# Link232-wifi-c64.net
KiCad netlist of a schematic drawn in EAGLE
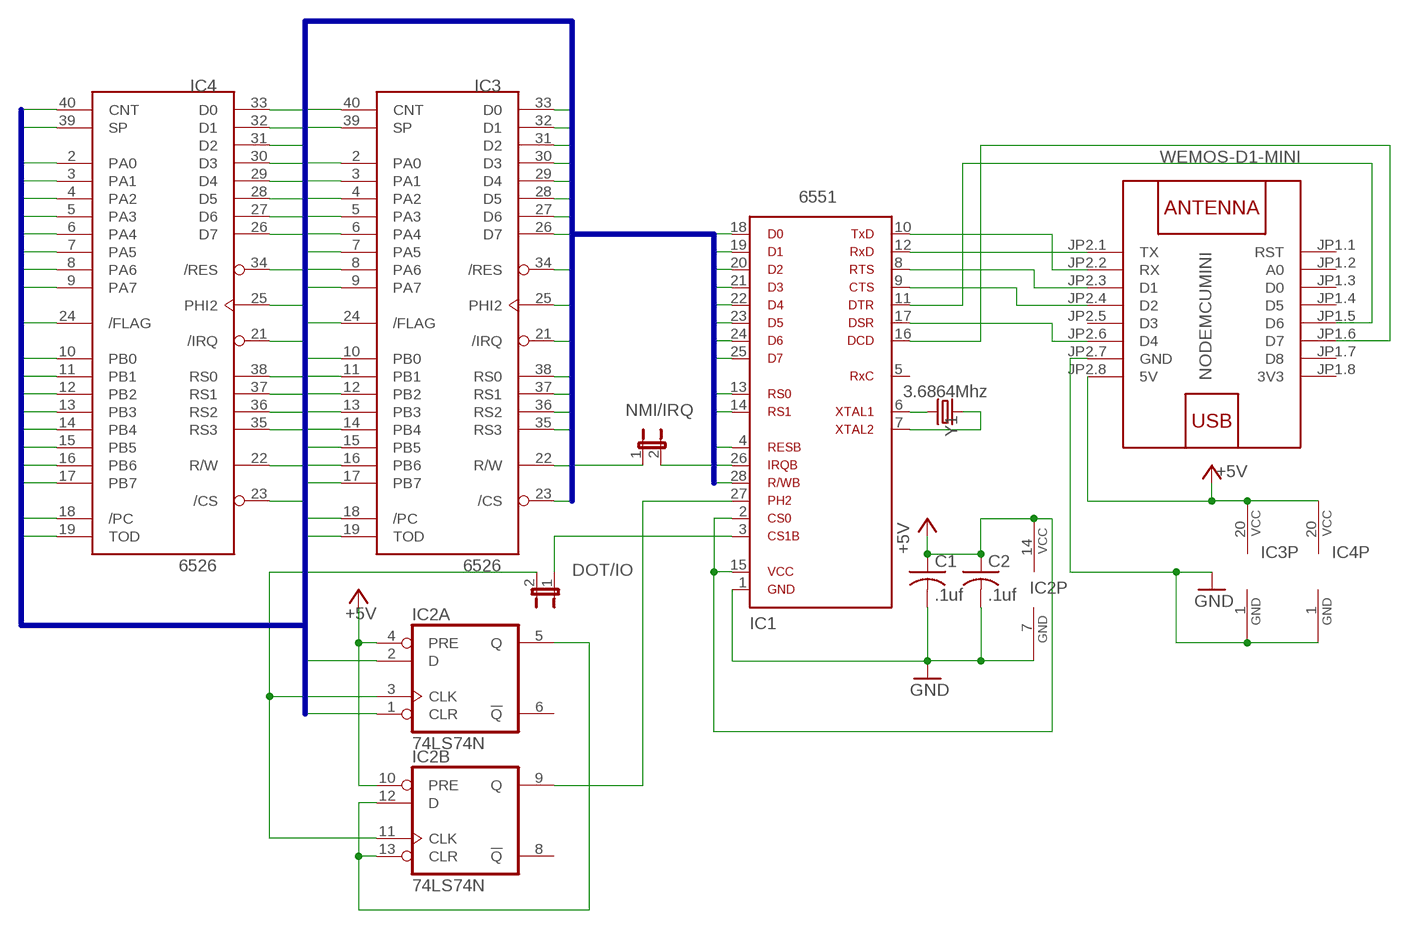
[diagram p0: schematic, sheet 1]

(export (version "E")
  (design (tool "Eeschema 10.0.6"))
  (components
    (comp (ref "C1")
      (value ".1uf")
      (footprint "eagle-import:C050-024X044")
      (libsource (lib "eagle-import") (part "C-US050-024X044"))
    )
    (comp (ref "C2")
      (value ".1uf")
      (footprint "eagle-import:C050-024X044")
      (libsource (lib "eagle-import") (part "C-US050-024X044"))
    )
    (comp (ref "IC1")
      (value "6551")
      (footprint "eagle-import:6551")
      (libsource (lib "eagle-import") (part "6551"))
    )
    (comp (ref "IC2")
      (value "74LS74N")
      (footprint "eagle-import:DIL14")
      (libsource (lib "eagle-import") (part "7474NLS"))
    )
    (comp (ref "IC3")
      (value "6526")
      (footprint "eagle-import:DIP40")
      (libsource (lib "eagle-import") (part "6526"))
    )
    (comp (ref "IC4")
      (value "6526")
      (footprint "eagle-import:DIP40")
      (libsource (lib "eagle-import") (part "6526"))
    )
    (comp (ref "JP1")
      (value "NMI/IRQ")
      (footprint "eagle-import:JP1")
      (libsource (lib "eagle-import") (part "JP1E"))
    )
    (comp (ref "JP2")
      (value "DOT/IO")
      (footprint "eagle-import:JP1")
      (libsource (lib "eagle-import") (part "JP1E"))
    )
    (comp (ref "NODEMCUMINI")
      (value "WEMOS-D1-MINI")
      (footprint "eagle-import:WEMOS-D1-MINI")
      (libsource (lib "eagle-import") (part "WEMOS-D1-MINI"))
    )
    (comp (ref "Y1")
      (value "3.6864Mhz")
      (footprint "eagle-import:HC49US")
      (libsource (lib "eagle-import") (part "CRYSTALPTH-HC49US"))
    )
  )
  (nets
    (net (code "1") (name "+5V") (class "Default")
      (node (ref "C1") (pin "1") (pinfunction "1_1") (pintype "passive"))
      (node (ref "C2") (pin "1") (pinfunction "1_1") (pintype "passive"))
      (node (ref "IC1") (pin "15") (pinfunction "15_15") (pintype "passive"))
      (node (ref "IC1") (pin "2") (pinfunction "2_2") (pintype "passive"))
      (node (ref "IC2") (pin "10") (pinfunction "PRE_10") (pintype "input"))
      (node (ref "IC2") (pin "14") (pinfunction "VCC_14") (pintype "power_in"))
      (node (ref "IC2") (pin "4") (pinfunction "PRE_4") (pintype "input"))
      (node (ref "IC3") (pin "20") (pinfunction "VCC_20") (pintype "power_in"))
      (node (ref "IC4") (pin "20") (pinfunction "VCC_20") (pintype "power_in"))
      (node (ref "NODEMCUMINI") (pin "JP2.8") (pinfunction "5V_JP2.8") (pintype "power_in"))
    )
    (net (code "2") (name "/3V3") (class "Default")
      (node (ref "NODEMCUMINI") (pin "JP1.8") (pinfunction "3V3_JP1.8") (pintype "power_in"))
    )
    (net (code "3") (name "/CNT") (class "Default")
      (node (ref "IC3") (pin "40") (pinfunction "CNT_40") (pintype "input"))
      (node (ref "IC4") (pin "40") (pinfunction "CNT_40") (pintype "input"))
    )
    (net (code "4") (name "/D0") (class "Default")
      (node (ref "IC1") (pin "18") (pinfunction "18_18") (pintype "passive"))
      (node (ref "IC3") (pin "33") (pinfunction "D0_33") (pintype "bidirectional"))
      (node (ref "IC4") (pin "33") (pinfunction "D0_33") (pintype "bidirectional"))
    )
    (net (code "5") (name "/D1") (class "Default")
      (node (ref "IC1") (pin "19") (pinfunction "19_19") (pintype "passive"))
      (node (ref "IC3") (pin "32") (pinfunction "D1_32") (pintype "bidirectional"))
      (node (ref "IC4") (pin "32") (pinfunction "D1_32") (pintype "bidirectional"))
    )
    (net (code "6") (name "/D2") (class "Default")
      (node (ref "IC1") (pin "20") (pinfunction "20_20") (pintype "passive"))
      (node (ref "IC3") (pin "31") (pinfunction "D2_31") (pintype "bidirectional"))
      (node (ref "IC4") (pin "31") (pinfunction "D2_31") (pintype "bidirectional"))
    )
    (net (code "7") (name "/D3") (class "Default")
      (node (ref "IC1") (pin "21") (pinfunction "21_21") (pintype "passive"))
      (node (ref "IC3") (pin "30") (pinfunction "D3_30") (pintype "bidirectional"))
      (node (ref "IC4") (pin "30") (pinfunction "D3_30") (pintype "bidirectional"))
    )
    (net (code "8") (name "/D4") (class "Default")
      (node (ref "IC1") (pin "22") (pinfunction "22_22") (pintype "passive"))
      (node (ref "IC3") (pin "29") (pinfunction "D4_29") (pintype "bidirectional"))
      (node (ref "IC4") (pin "29") (pinfunction "D4_29") (pintype "bidirectional"))
    )
    (net (code "9") (name "/D5") (class "Default")
      (node (ref "IC1") (pin "23") (pinfunction "23_23") (pintype "passive"))
      (node (ref "IC3") (pin "28") (pinfunction "D5_28") (pintype "bidirectional"))
      (node (ref "IC4") (pin "28") (pinfunction "D5_28") (pintype "bidirectional"))
    )
    (net (code "10") (name "/D6") (class "Default")
      (node (ref "IC1") (pin "24") (pinfunction "24_24") (pintype "passive"))
      (node (ref "IC3") (pin "27") (pinfunction "D6_27") (pintype "bidirectional"))
      (node (ref "IC4") (pin "27") (pinfunction "D6_27") (pintype "bidirectional"))
    )
    (net (code "11") (name "/D7") (class "Default")
      (node (ref "IC1") (pin "25") (pinfunction "25_25") (pintype "passive"))
      (node (ref "IC3") (pin "26") (pinfunction "D7_26") (pintype "bidirectional"))
      (node (ref "IC4") (pin "26") (pinfunction "D7_26") (pintype "bidirectional"))
    )
    (net (code "12") (name "/IRQ") (class "Default")
      (node (ref "IC3") (pin "21") (pinfunction "/IRQ_21") (pintype "open_collector"))
      (node (ref "IC4") (pin "21") (pinfunction "/IRQ_21") (pintype "open_collector"))
      (node (ref "JP1") (pin "1") (pinfunction "1_1") (pintype "passive"))
    )
    (net (code "13") (name "/PA0") (class "Default")
      (node (ref "IC3") (pin "2") (pinfunction "PA0_2") (pintype "bidirectional"))
      (node (ref "IC4") (pin "2") (pinfunction "PA0_2") (pintype "bidirectional"))
    )
    (net (code "14") (name "/PA1") (class "Default")
      (node (ref "IC3") (pin "3") (pinfunction "PA1_3") (pintype "bidirectional"))
      (node (ref "IC4") (pin "3") (pinfunction "PA1_3") (pintype "bidirectional"))
    )
    (net (code "15") (name "/PA2") (class "Default")
      (node (ref "IC3") (pin "4") (pinfunction "PA2_4") (pintype "bidirectional"))
      (node (ref "IC4") (pin "4") (pinfunction "PA2_4") (pintype "bidirectional"))
    )
    (net (code "16") (name "/PA3") (class "Default")
      (node (ref "IC3") (pin "5") (pinfunction "PA3_5") (pintype "bidirectional"))
      (node (ref "IC4") (pin "5") (pinfunction "PA3_5") (pintype "bidirectional"))
    )
    (net (code "17") (name "/PA4") (class "Default")
      (node (ref "IC3") (pin "6") (pinfunction "PA4_6") (pintype "bidirectional"))
      (node (ref "IC4") (pin "6") (pinfunction "PA4_6") (pintype "bidirectional"))
    )
    (net (code "18") (name "/PA5") (class "Default")
      (node (ref "IC3") (pin "7") (pinfunction "PA5_7") (pintype "bidirectional"))
      (node (ref "IC4") (pin "7") (pinfunction "PA5_7") (pintype "bidirectional"))
    )
    (net (code "19") (name "/PA6") (class "Default")
      (node (ref "IC3") (pin "8") (pinfunction "PA6_8") (pintype "bidirectional"))
      (node (ref "IC4") (pin "8") (pinfunction "PA6_8") (pintype "bidirectional"))
    )
    (net (code "20") (name "/PA7") (class "Default")
      (node (ref "IC3") (pin "9") (pinfunction "PA7_9") (pintype "bidirectional"))
      (node (ref "IC4") (pin "9") (pinfunction "PA7_9") (pintype "bidirectional"))
    )
    (net (code "21") (name "/PB0") (class "Default")
      (node (ref "IC3") (pin "10") (pinfunction "PB0_10") (pintype "bidirectional"))
      (node (ref "IC4") (pin "10") (pinfunction "PB0_10") (pintype "bidirectional"))
    )
    (net (code "22") (name "/PB1") (class "Default")
      (node (ref "IC3") (pin "11") (pinfunction "PB1_11") (pintype "bidirectional"))
      (node (ref "IC4") (pin "11") (pinfunction "PB1_11") (pintype "bidirectional"))
    )
    (net (code "23") (name "/PB2") (class "Default")
      (node (ref "IC3") (pin "12") (pinfunction "PB2_12") (pintype "bidirectional"))
      (node (ref "IC4") (pin "12") (pinfunction "PB2_12") (pintype "bidirectional"))
    )
    (net (code "24") (name "/PB3") (class "Default")
      (node (ref "IC3") (pin "13") (pinfunction "PB3_13") (pintype "bidirectional"))
      (node (ref "IC4") (pin "13") (pinfunction "PB3_13") (pintype "bidirectional"))
    )
    (net (code "25") (name "/PB4") (class "Default")
      (node (ref "IC3") (pin "14") (pinfunction "PB4_14") (pintype "bidirectional"))
      (node (ref "IC4") (pin "14") (pinfunction "PB4_14") (pintype "bidirectional"))
    )
    (net (code "26") (name "/PB5") (class "Default")
      (node (ref "IC3") (pin "15") (pinfunction "PB5_15") (pintype "bidirectional"))
      (node (ref "IC4") (pin "15") (pinfunction "PB5_15") (pintype "bidirectional"))
    )
    (net (code "27") (name "/PB6") (class "Default")
      (node (ref "IC3") (pin "16") (pinfunction "PB6_16") (pintype "bidirectional"))
      (node (ref "IC4") (pin "16") (pinfunction "PB6_16") (pintype "bidirectional"))
    )
    (net (code "28") (name "/PB7") (class "Default")
      (node (ref "IC3") (pin "17") (pinfunction "PB7_17") (pintype "bidirectional"))
      (node (ref "IC4") (pin "17") (pinfunction "PB7_17") (pintype "bidirectional"))
    )
    (net (code "29") (name "/PHI2") (class "Default")
      (node (ref "IC2") (pin "1") (pinfunction "CLR_1") (pintype "input"))
      (node (ref "IC2") (pin "2") (pinfunction "D_2") (pintype "input"))
      (node (ref "IC3") (pin "25") (pinfunction "PHI2_25") (pintype "input"))
      (node (ref "IC4") (pin "25") (pinfunction "PHI2_25") (pintype "input"))
    )
    (net (code "30") (name "/RES") (class "Default")
      (node (ref "IC1") (pin "4") (pinfunction "4_4") (pintype "passive"))
      (node (ref "IC3") (pin "34") (pinfunction "/RES_34") (pintype "input"))
      (node (ref "IC4") (pin "34") (pinfunction "/RES_34") (pintype "input"))
    )
    (net (code "31") (name "/RS0") (class "Default")
      (node (ref "IC1") (pin "13") (pinfunction "13_13") (pintype "passive"))
      (node (ref "IC3") (pin "38") (pinfunction "RS0_38") (pintype "input"))
      (node (ref "IC4") (pin "38") (pinfunction "RS0_38") (pintype "input"))
    )
    (net (code "32") (name "/RS1") (class "Default")
      (node (ref "IC1") (pin "14") (pinfunction "14_14") (pintype "passive"))
      (node (ref "IC3") (pin "37") (pinfunction "RS1_37") (pintype "input"))
      (node (ref "IC4") (pin "37") (pinfunction "RS1_37") (pintype "input"))
    )
    (net (code "33") (name "/RS2") (class "Default")
      (node (ref "IC3") (pin "36") (pinfunction "RS2_36") (pintype "input"))
      (node (ref "IC4") (pin "36") (pinfunction "RS2_36") (pintype "input"))
    )
    (net (code "34") (name "/RS3") (class "Default")
      (node (ref "IC3") (pin "35") (pinfunction "RS3_35") (pintype "input"))
      (node (ref "IC4") (pin "35") (pinfunction "RS3_35") (pintype "input"))
    )
    (net (code "35") (name "/RW") (class "Default")
      (node (ref "IC1") (pin "28") (pinfunction "28_28") (pintype "passive"))
      (node (ref "IC3") (pin "22") (pinfunction "R/W_22") (pintype "input"))
      (node (ref "IC4") (pin "22") (pinfunction "R/W_22") (pintype "input"))
    )
    (net (code "36") (name "/SP") (class "Default")
      (node (ref "IC3") (pin "39") (pinfunction "SP_39") (pintype "bidirectional"))
      (node (ref "IC4") (pin "39") (pinfunction "SP_39") (pintype "bidirectional"))
    )
    (net (code "37") (name "/TOD") (class "Default")
      (node (ref "IC3") (pin "19") (pinfunction "TOD_19") (pintype "bidirectional"))
      (node (ref "IC4") (pin "19") (pinfunction "TOD_19") (pintype "bidirectional"))
    )
    (net (code "38") (name "/{slash}CS") (class "Default")
      (node (ref "IC3") (pin "23") (pinfunction "/CS_23") (pintype "input"))
      (node (ref "IC4") (pin "23") (pinfunction "/CS_23") (pintype "input"))
    )
    (net (code "39") (name "/{slash}FLAG") (class "Default")
      (node (ref "IC3") (pin "24") (pinfunction "/FLAG_24") (pintype "input"))
      (node (ref "IC4") (pin "24") (pinfunction "/FLAG_24") (pintype "input"))
    )
    (net (code "40") (name "/{slash}PC") (class "Default")
      (node (ref "IC3") (pin "18") (pinfunction "/PC_18") (pintype "bidirectional"))
      (node (ref "IC4") (pin "18") (pinfunction "/PC_18") (pintype "bidirectional"))
    )
    (net (code "41") (name "GND") (class "Default")
      (node (ref "C1") (pin "2") (pinfunction "2_2") (pintype "passive"))
      (node (ref "C2") (pin "2") (pinfunction "2_2") (pintype "passive"))
      (node (ref "IC1") (pin "1") (pinfunction "1_1") (pintype "passive"))
      (node (ref "IC2") (pin "7") (pinfunction "GND_7") (pintype "power_in"))
      (node (ref "IC3") (pin "1") (pinfunction "GND_1") (pintype "power_in"))
      (node (ref "IC4") (pin "1") (pinfunction "GND_1") (pintype "power_in"))
      (node (ref "NODEMCUMINI") (pin "JP2.7") (pinfunction "GND_JP2.7") (pintype "power_in"))
    )
    (net (code "42") (name "Net-(IC1-Pad3)") (class "Default")
      (node (ref "IC1") (pin "3") (pinfunction "3_3") (pintype "passive"))
      (node (ref "JP2") (pin "1") (pinfunction "1_1") (pintype "passive"))
    )
    (net (code "43") (name "Net-(IC1-Pad6)") (class "Default")
      (node (ref "IC1") (pin "6") (pinfunction "6_6") (pintype "passive"))
      (node (ref "Y1") (pin "2") (pinfunction "2_2") (pintype "passive"))
    )
    (net (code "44") (name "Net-(IC1-Pad7)") (class "Default")
      (node (ref "IC1") (pin "7") (pinfunction "7_7") (pintype "passive"))
      (node (ref "Y1") (pin "1") (pinfunction "1_1") (pintype "passive"))
    )
    (net (code "45") (name "Net-(IC1-Pad26)") (class "Default")
      (node (ref "IC1") (pin "26") (pinfunction "26_26") (pintype "passive"))
      (node (ref "JP1") (pin "2") (pinfunction "2_2") (pintype "passive"))
    )
    (net (code "46") (name "Net-(IC2A-CLK)") (class "Default")
      (node (ref "IC2") (pin "11") (pinfunction "CLK_11") (pintype "input"))
      (node (ref "IC2") (pin "3") (pinfunction "CLK_3") (pintype "input"))
      (node (ref "JP2") (pin "2") (pinfunction "2_2") (pintype "passive"))
    )
    (net (code "47") (name "Net-(IC2A-Q)") (class "Default")
      (node (ref "IC2") (pin "12") (pinfunction "D_12") (pintype "input"))
      (node (ref "IC2") (pin "13") (pinfunction "CLR_13") (pintype "input"))
      (node (ref "IC2") (pin "5") (pinfunction "Q_5") (pintype "output"))
    )
    (net (code "48") (name "Net-(IC2B-Q)") (class "Default")
      (node (ref "IC1") (pin "27") (pinfunction "27_27") (pintype "passive"))
      (node (ref "IC2") (pin "9") (pinfunction "Q_9") (pintype "output"))
    )
    (net (code "49") (name "Net-(NODEMCUMINI-D1)") (class "Default")
      (node (ref "IC1") (pin "8") (pinfunction "8_8") (pintype "passive"))
      (node (ref "NODEMCUMINI") (pin "JP2.3") (pinfunction "D1_JP2.3") (pintype "bidirectional"))
    )
    (net (code "50") (name "Net-(NODEMCUMINI-D2)") (class "Default")
      (node (ref "IC1") (pin "9") (pinfunction "9_9") (pintype "passive"))
      (node (ref "NODEMCUMINI") (pin "JP2.4") (pinfunction "D2_JP2.4") (pintype "bidirectional"))
    )
    (net (code "51") (name "Net-(NODEMCUMINI-D4)") (class "Default")
      (node (ref "IC1") (pin "17") (pinfunction "17_17") (pintype "passive"))
      (node (ref "NODEMCUMINI") (pin "JP2.6") (pinfunction "D4_JP2.6") (pintype "bidirectional"))
    )
    (net (code "52") (name "Net-(NODEMCUMINI-D6)") (class "Default")
      (node (ref "IC1") (pin "11") (pinfunction "11_11") (pintype "passive"))
      (node (ref "NODEMCUMINI") (pin "JP1.5") (pinfunction "D6_JP1.5") (pintype "bidirectional"))
    )
    (net (code "53") (name "Net-(NODEMCUMINI-D7)") (class "Default")
      (node (ref "IC1") (pin "16") (pinfunction "16_16") (pintype "passive"))
      (node (ref "NODEMCUMINI") (pin "JP1.6") (pinfunction "D7_JP1.6") (pintype "bidirectional"))
    )
    (net (code "54") (name "Net-(NODEMCUMINI-RX)") (class "Default")
      (node (ref "IC1") (pin "10") (pinfunction "10_10") (pintype "passive"))
      (node (ref "NODEMCUMINI") (pin "JP2.2") (pinfunction "RX_JP2.2") (pintype "bidirectional"))
    )
    (net (code "55") (name "Net-(NODEMCUMINI-TX)") (class "Default")
      (node (ref "IC1") (pin "12") (pinfunction "12_12") (pintype "passive"))
      (node (ref "NODEMCUMINI") (pin "JP2.1") (pinfunction "TX_JP2.1") (pintype "bidirectional"))
    )
    (net (code "56") (name "unconnected-(IC1-Pad5)") (class "Default")
      (node (ref "IC1") (pin "5") (pinfunction "5_5") (pintype "passive"))
    )
    (net (code "57") (name "unconnected-(IC2A-~{Q}-Pad6)") (class "Default")
      (node (ref "IC2") (pin "6") (pinfunction "~{Q}_6") (pintype "output"))
    )
    (net (code "58") (name "unconnected-(IC2B-~{Q}-Pad8)") (class "Default")
      (node (ref "IC2") (pin "8") (pinfunction "~{Q}_8") (pintype "output"))
    )
    (net (code "59") (name "unconnected-(NODEMCUMINI-A0-PadJP1.2)") (class "Default")
      (node (ref "NODEMCUMINI") (pin "JP1.2") (pinfunction "A0_JP1.2") (pintype "bidirectional"))
    )
    (net (code "60") (name "unconnected-(NODEMCUMINI-D0-PadJP1.3)") (class "Default")
      (node (ref "NODEMCUMINI") (pin "JP1.3") (pinfunction "D0_JP1.3") (pintype "bidirectional"))
    )
    (net (code "61") (name "unconnected-(NODEMCUMINI-D3-PadJP2.5)") (class "Default")
      (node (ref "NODEMCUMINI") (pin "JP2.5") (pinfunction "D3_JP2.5") (pintype "bidirectional"))
    )
    (net (code "62") (name "unconnected-(NODEMCUMINI-D5-PadJP1.4)") (class "Default")
      (node (ref "NODEMCUMINI") (pin "JP1.4") (pinfunction "D5_JP1.4") (pintype "bidirectional"))
    )
    (net (code "63") (name "unconnected-(NODEMCUMINI-D8-PadJP1.7)") (class "Default")
      (node (ref "NODEMCUMINI") (pin "JP1.7") (pinfunction "D8_JP1.7") (pintype "bidirectional"))
    )
    (net (code "64") (name "unconnected-(NODEMCUMINI-RST-PadJP1.1)") (class "Default")
      (node (ref "NODEMCUMINI") (pin "JP1.1") (pinfunction "RST_JP1.1") (pintype "bidirectional"))
    )
  )
)
